# main.net
KiCad netlist of a schematic drawn in Altium Designer
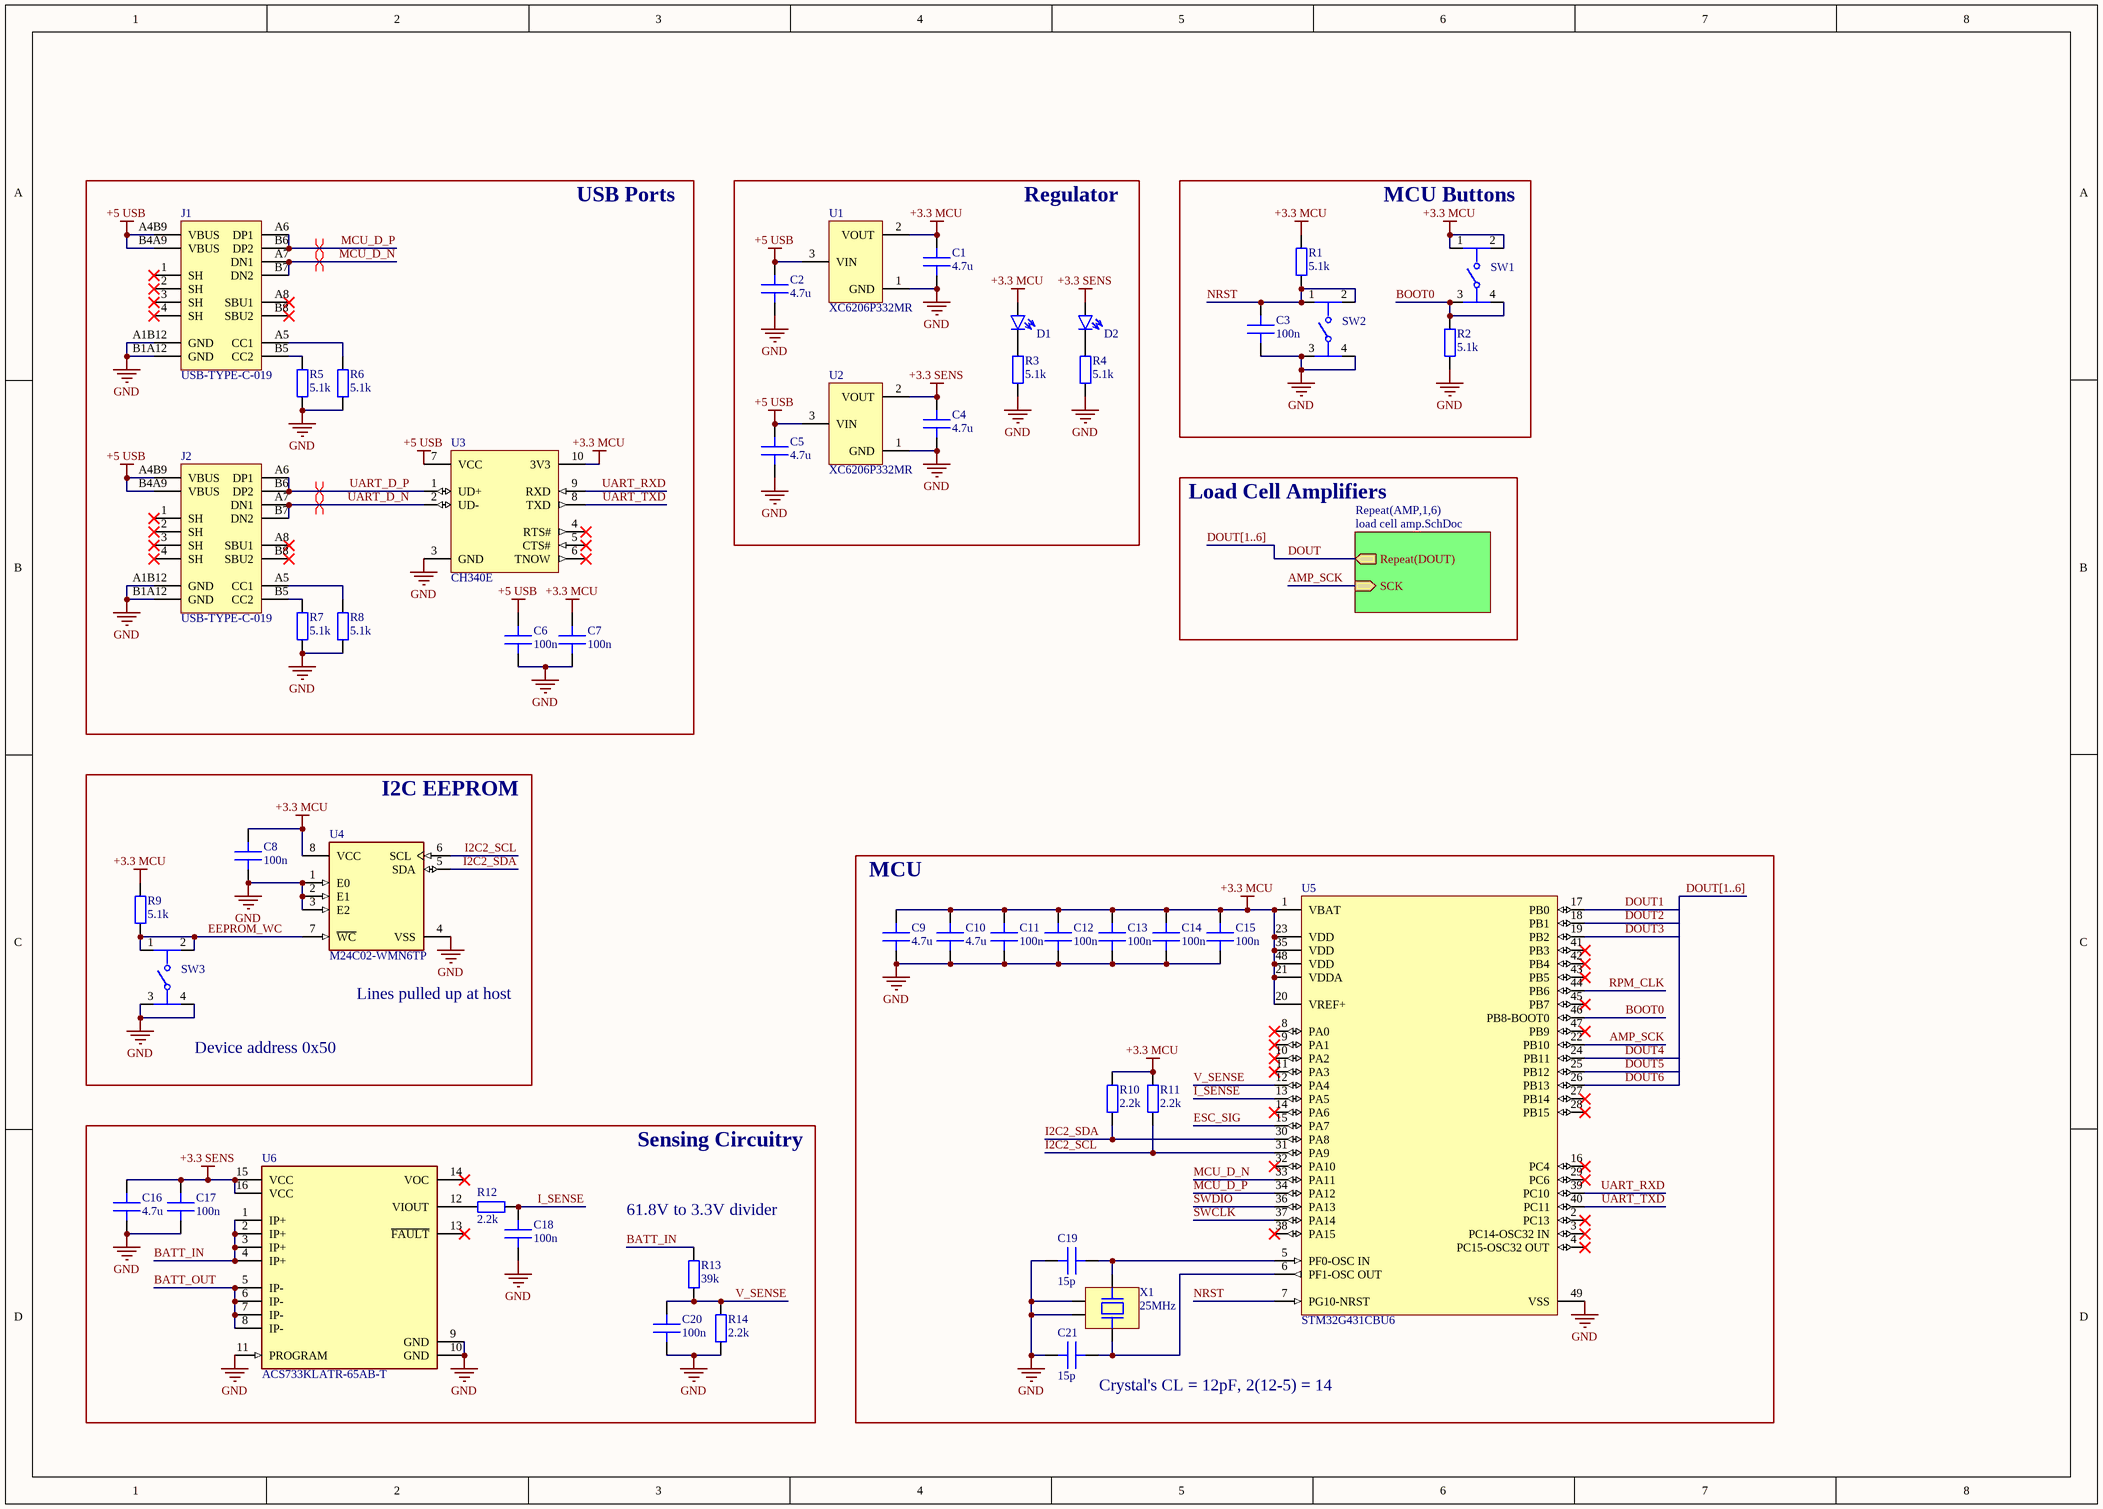
[diagram p0: main.SchDoc]

(export (version "E")
  (design (tool "Eeschema 10.0.6"))
  (components
    (comp (ref "C1")
      (value "4.7u")
      (footprint "IPC C C0603 NO SILK")
      (libsource (lib "JLCPCB Library") (part "Generic CAP 0603"))
    )
    (comp (ref "C2")
      (value "4.7u")
      (footprint "IPC C C0603 NO SILK")
      (libsource (lib "JLCPCB Library") (part "Generic CAP 0603"))
    )
    (comp (ref "C3")
      (value "100n")
      (footprint "IPC C C0402 NO SILK")
      (libsource (lib "JLCPCB Library") (part "Generic CAP 0402"))
    )
    (comp (ref "C4")
      (value "4.7u")
      (footprint "IPC C C0603 NO SILK")
      (libsource (lib "JLCPCB Library") (part "Generic CAP 0603"))
    )
    (comp (ref "C5")
      (value "4.7u")
      (footprint "IPC C C0603 NO SILK")
      (libsource (lib "JLCPCB Library") (part "Generic CAP 0603"))
    )
    (comp (ref "C6")
      (value "100n")
      (footprint "IPC C C0402 NO SILK")
      (libsource (lib "JLCPCB Library") (part "Generic CAP 0402"))
    )
    (comp (ref "C7")
      (value "100n")
      (footprint "IPC C C0402 NO SILK")
      (libsource (lib "JLCPCB Library") (part "Generic CAP 0402"))
    )
    (comp (ref "C8")
      (value "100n")
      (footprint "IPC C C0402 NO SILK")
      (libsource (lib "JLCPCB Library") (part "Generic CAP 0402"))
    )
    (comp (ref "C9")
      (value "4.7u")
      (footprint "IPC C C0603 NO SILK")
      (libsource (lib "JLCPCB Library") (part "Generic CAP 0603"))
    )
    (comp (ref "C10")
      (value "4.7u")
      (footprint "IPC C C0603 NO SILK")
      (libsource (lib "JLCPCB Library") (part "Generic CAP 0603"))
    )
    (comp (ref "C11")
      (value "100n")
      (footprint "IPC C C0402 NO SILK")
      (libsource (lib "JLCPCB Library") (part "Generic CAP 0402"))
    )
    (comp (ref "C12")
      (value "100n")
      (footprint "IPC C C0402 NO SILK")
      (libsource (lib "JLCPCB Library") (part "Generic CAP 0402"))
    )
    (comp (ref "C13")
      (value "100n")
      (footprint "IPC C C0402 NO SILK")
      (libsource (lib "JLCPCB Library") (part "Generic CAP 0402"))
    )
    (comp (ref "C14")
      (value "100n")
      (footprint "IPC C C0402 NO SILK")
      (libsource (lib "JLCPCB Library") (part "Generic CAP 0402"))
    )
    (comp (ref "C15")
      (value "100n")
      (footprint "IPC C C0402 NO SILK")
      (libsource (lib "JLCPCB Library") (part "Generic CAP 0402"))
    )
    (comp (ref "C16")
      (value "4.7u")
      (footprint "IPC C C0603 NO SILK")
      (libsource (lib "JLCPCB Library") (part "Generic CAP 0603"))
    )
    (comp (ref "C17")
      (value "100n")
      (footprint "IPC C C0402 NO SILK")
      (libsource (lib "JLCPCB Library") (part "Generic CAP 0402"))
    )
    (comp (ref "C18")
      (value "100n")
      (footprint "IPC C C0402 NO SILK")
      (libsource (lib "JLCPCB Library") (part "Generic CAP 0402"))
    )
    (comp (ref "C19")
      (value "15p")
      (footprint "IPC C C0402 NO SILK")
      (libsource (lib "JLCPCB Library") (part "Generic CAP 0402"))
    )
    (comp (ref "C20")
      (value "100n")
      (footprint "IPC C C0402 NO SILK")
      (libsource (lib "JLCPCB Library") (part "Generic CAP 0402"))
    )
    (comp (ref "C21")
      (value "15p")
      (footprint "IPC C C0402 NO SILK")
      (libsource (lib "JLCPCB Library") (part "Generic CAP 0402"))
    )
    (comp (ref "D1")
      (value "Generic LED 0603")
      (footprint "IPC C D0603")
      (libsource (lib "JLCPCB Library") (part "Generic LED 0603"))
    )
    (comp (ref "D2")
      (value "Generic LED 0603")
      (footprint "IPC C D0603")
      (libsource (lib "JLCPCB Library") (part "Generic LED 0603"))
    )
    (comp (ref "J1")
      (value "USB-TYPE-C-019")
      (footprint "USB-TYPE-C-12+4P")
      (fields (field (name "MANUFACTURER") "DEALON(德艺隆)"))
      (libsource (lib "JLCPCB Library") (part "USB-TYPE-C-019"))
    )
    (comp (ref "J2")
      (value "USB-TYPE-C-019")
      (footprint "USB-TYPE-C-12+4P")
      (fields (field (name "MANUFACTURER") "DEALON(德艺隆)"))
      (libsource (lib "JLCPCB Library") (part "USB-TYPE-C-019"))
    )
    (comp (ref "R1")
      (value "5.1k")
      (footprint "IPC C R0402 NO SILK")
      (libsource (lib "JLCPCB Library") (part "Generic RES 0402"))
    )
    (comp (ref "R2")
      (value "5.1k")
      (footprint "IPC C R0402 NO SILK")
      (libsource (lib "JLCPCB Library") (part "Generic RES 0402"))
    )
    (comp (ref "R3")
      (value "5.1k")
      (footprint "IPC C R0402 NO SILK")
      (libsource (lib "JLCPCB Library") (part "Generic RES 0402"))
    )
    (comp (ref "R4")
      (value "5.1k")
      (footprint "IPC C R0402 NO SILK")
      (libsource (lib "JLCPCB Library") (part "Generic RES 0402"))
    )
    (comp (ref "R5")
      (value "5.1k")
      (footprint "IPC C R0402 NO SILK")
      (libsource (lib "JLCPCB Library") (part "Generic RES 0402"))
    )
    (comp (ref "R6")
      (value "5.1k")
      (footprint "IPC C R0402 NO SILK")
      (libsource (lib "JLCPCB Library") (part "Generic RES 0402"))
    )
    (comp (ref "R7")
      (value "5.1k")
      (footprint "IPC C R0402 NO SILK")
      (libsource (lib "JLCPCB Library") (part "Generic RES 0402"))
    )
    (comp (ref "R8")
      (value "5.1k")
      (footprint "IPC C R0402 NO SILK")
      (libsource (lib "JLCPCB Library") (part "Generic RES 0402"))
    )
    (comp (ref "R9")
      (value "5.1k")
      (footprint "IPC C R0402 NO SILK")
      (libsource (lib "JLCPCB Library") (part "Generic RES 0402"))
    )
    (comp (ref "R10")
      (value "2.2k")
      (footprint "IPC C R0402 NO SILK")
      (libsource (lib "JLCPCB Library") (part "Generic RES 0402"))
    )
    (comp (ref "R11")
      (value "2.2k")
      (footprint "IPC C R0402 NO SILK")
      (libsource (lib "JLCPCB Library") (part "Generic RES 0402"))
    )
    (comp (ref "R12")
      (value "2.2k")
      (footprint "IPC C R0402 NO SILK")
      (libsource (lib "JLCPCB Library") (part "Generic RES 0402"))
    )
    (comp (ref "R13")
      (value "39k")
      (footprint "IPC C R0402 NO SILK")
      (libsource (lib "JLCPCB Library") (part "Generic RES 0402"))
    )
    (comp (ref "R14")
      (value "2.2k")
      (footprint "IPC C R0402 NO SILK")
      (libsource (lib "JLCPCB Library") (part "Generic RES 0402"))
    )
    (comp (ref "SW1")
      (value "PTS810SJM250SMTRLFS")
      (footprint "FP-PTS810SJM250SMTRLFS-MFG")
      (description "SWITCH TACTILE SPST-NO 0.05A 16V")
      (libsource (lib "Altium Content Vault") (part "1adf0dd01260c80cf25a44bfd6b99ba"))
    )
    (comp (ref "SW2")
      (value "PTS810SJM250SMTRLFS")
      (footprint "FP-PTS810SJM250SMTRLFS-MFG")
      (description "SWITCH TACTILE SPST-NO 0.05A 16V")
      (libsource (lib "Altium Content Vault") (part "1adf0dd01260c80cf25a44bfd6b99ba"))
    )
    (comp (ref "SW3")
      (value "PTS810SJM250SMTRLFS")
      (footprint "FP-PTS810SJM250SMTRLFS-MFG")
      (description "SWITCH TACTILE SPST-NO 0.05A 16V")
      (libsource (lib "Altium Content Vault") (part "1adf0dd01260c80cf25a44bfd6b99ba"))
    )
    (comp (ref "U1")
      (value "XC6206P332MR")
      (footprint "SOT23-3")
      (fields (field (name "MANUFACTURER") "TOREX(特瑞仕)"))
      (libsource (lib "JLCPCB Library") (part "3.3V Regulator XC6206P332MR_C5446"))
    )
    (comp (ref "U2")
      (value "XC6206P332MR")
      (footprint "SOT23-3")
      (fields (field (name "MANUFACTURER") "TOREX(特瑞仕)"))
      (libsource (lib "JLCPCB Library") (part "3.3V Regulator XC6206P332MR_C5446"))
    )
    (comp (ref "U3")
      (value "CH340E")
      (footprint "MSOP-UN10_L")
      (libsource (lib "JLCPCB Library") (part "CH340E"))
    )
    (comp (ref "U4")
      (value "M24C02-WMN6TP")
      (footprint "FP-SO8N-SO-A-MFG")
      (description "IC EEPROM 2K I2C 400KHZ 8SO")
      (fields
        (field (name "MANUFACTURER") "STMicroelectronics")
        (field (name "OCTOPART") "https://octopart.com/m24c02-wmn6tp-stmicroelectronics-55404516")
      )
      (libsource (lib "Altium Content Vault") (part "6c91e1c1613830ec3abd94c18390ae3"))
    )
    (comp (ref "U5")
      (value "STM32G431CBU6")
      (footprint "QFN50P700X700X60_HS-49L")
      (libsource (lib "JLCPCB Library") (part "STM32G431CBU6"))
    )
    (comp (ref "U6")
      (value "ACS733KLATR-65AB-T")
      (footprint "FP-LA-16-MFG")
      (description "AUTOMOTIVE GRADE HIGH BANDWIDTH")
      (libsource (lib "Altium Content Vault") (part "bea2a1565df5e50c2a3c76684115569"))
    )
    (comp (ref "X1")
      (value "25MHz")
      (footprint "OSC-SMD_4P-L3.2-W2.5-BL")
      (fields (field (name "MANUFACTURER") "YXC(扬兴晶振)") (field (name "MANUFACTURER PART") "X322525MOB4SI"))
      (libsource (lib "JLCPCB Library") (part "Crystal 25MHz X322525MOB4SI"))
    )
  )
  (nets
    (net (code "1") (name "+3.3 MCU") (class "Default")
      (node (ref "C1") (pin "2") (pinfunction "2_2") (pintype "passive"))
      (node (ref "C10") (pin "2") (pinfunction "2_2") (pintype "passive"))
      (node (ref "C11") (pin "2") (pinfunction "2_2") (pintype "passive"))
      (node (ref "C12") (pin "2") (pinfunction "2_2") (pintype "passive"))
      (node (ref "C13") (pin "2") (pinfunction "2_2") (pintype "passive"))
      (node (ref "C14") (pin "2") (pinfunction "2_2") (pintype "passive"))
      (node (ref "C15") (pin "2") (pinfunction "2_2") (pintype "passive"))
      (node (ref "C7") (pin "2") (pinfunction "2_2") (pintype "passive"))
      (node (ref "C8") (pin "2") (pinfunction "2_2") (pintype "passive"))
      (node (ref "C9") (pin "2") (pinfunction "2_2") (pintype "passive"))
      (node (ref "D1") (pin "1") (pinfunction "A_1") (pintype "passive"))
      (node (ref "R1") (pin "2") (pinfunction "2_2") (pintype "passive"))
      (node (ref "R10") (pin "2") (pinfunction "2_2") (pintype "passive"))
      (node (ref "R11") (pin "2") (pinfunction "2_2") (pintype "passive"))
      (node (ref "R9") (pin "2") (pinfunction "2_2") (pintype "passive"))
      (node (ref "SW1") (pin "1") (pinfunction "1_1") (pintype "passive"))
      (node (ref "SW1") (pin "2") (pinfunction "2_2") (pintype "passive"))
      (node (ref "U1") (pin "2") (pinfunction "VOUT_2") (pintype "power_in"))
      (node (ref "U3") (pin "10") (pinfunction "3V3_10") (pintype "power_in"))
      (node (ref "U4") (pin "8") (pinfunction "VCC_8") (pintype "power_in"))
      (node (ref "U5") (pin "1") (pinfunction "VBAT_1") (pintype "power_in"))
      (node (ref "U5") (pin "20") (pinfunction "VREF+_20") (pintype "passive"))
      (node (ref "U5") (pin "21") (pinfunction "VDDA_21") (pintype "power_in"))
      (node (ref "U5") (pin "23") (pinfunction "VDD_23") (pintype "power_in"))
      (node (ref "U5") (pin "35") (pinfunction "VDD_35") (pintype "power_in"))
      (node (ref "U5") (pin "48") (pinfunction "VDD_48") (pintype "power_in"))
    )
    (net (code "2") (name "+3.3 SENS") (class "Default")
      (node (ref "C16") (pin "2") (pinfunction "2_2") (pintype "passive"))
      (node (ref "C17") (pin "2") (pinfunction "2_2") (pintype "passive"))
      (node (ref "C4") (pin "2") (pinfunction "2_2") (pintype "passive"))
      (node (ref "D2") (pin "1") (pinfunction "A_1") (pintype "passive"))
      (node (ref "U2") (pin "2") (pinfunction "VOUT_2") (pintype "power_in"))
      (node (ref "U6") (pin "15") (pinfunction "VCC_15") (pintype "power_in"))
      (node (ref "U6") (pin "16") (pinfunction "VCC_16") (pintype "power_in"))
    )
    (net (code "3") (name "+5 USB") (class "Default")
      (node (ref "C2") (pin "2") (pinfunction "2_2") (pintype "passive"))
      (node (ref "C5") (pin "2") (pinfunction "2_2") (pintype "passive"))
      (node (ref "C6") (pin "2") (pinfunction "2_2") (pintype "passive"))
      (node (ref "J1") (pin "A4B9") (pinfunction "VBUS_A4B9") (pintype "power_in"))
      (node (ref "J1") (pin "B4A9") (pinfunction "VBUS_B4A9") (pintype "power_in"))
      (node (ref "J2") (pin "A4B9") (pinfunction "VBUS_A4B9") (pintype "power_in"))
      (node (ref "J2") (pin "B4A9") (pinfunction "VBUS_B4A9") (pintype "power_in"))
      (node (ref "U1") (pin "3") (pinfunction "VIN_3") (pintype "power_in"))
      (node (ref "U2") (pin "3") (pinfunction "VIN_3") (pintype "power_in"))
      (node (ref "U3") (pin "7") (pinfunction "VCC_7") (pintype "power_in"))
    )
    (net (code "4") (name "/AMP_SCK") (class "Default")
      (node (ref "U5") (pin "22") (pinfunction "PB10_22") (pintype "bidirectional"))
    )
    (net (code "5") (name "/BATT_IN") (class "Default")
      (node (ref "R13") (pin "2") (pinfunction "2_2") (pintype "passive"))
      (node (ref "U6") (pin "1") (pinfunction "IP+_1") (pintype "passive"))
      (node (ref "U6") (pin "2") (pinfunction "IP+_2") (pintype "passive"))
      (node (ref "U6") (pin "3") (pinfunction "IP+_3") (pintype "passive"))
      (node (ref "U6") (pin "4") (pinfunction "IP+_4") (pintype "passive"))
    )
    (net (code "6") (name "/BATT_OUT") (class "Default")
      (node (ref "U6") (pin "5") (pinfunction "IP-_5") (pintype "passive"))
      (node (ref "U6") (pin "6") (pinfunction "IP-_6") (pintype "passive"))
      (node (ref "U6") (pin "7") (pinfunction "IP-_7") (pintype "passive"))
      (node (ref "U6") (pin "8") (pinfunction "IP-_8") (pintype "passive"))
    )
    (net (code "7") (name "/BOOT0") (class "Default")
      (node (ref "R2") (pin "2") (pinfunction "2_2") (pintype "passive"))
      (node (ref "SW1") (pin "3") (pinfunction "3_3") (pintype "passive"))
      (node (ref "SW1") (pin "4") (pinfunction "4_4") (pintype "passive"))
      (node (ref "U5") (pin "46") (pinfunction "PB8-BOOT0_46") (pintype "bidirectional"))
    )
    (net (code "9") (name "/DOUT1") (class "Default")
      (node (ref "U5") (pin "17") (pinfunction "PB0_17") (pintype "bidirectional"))
    )
    (net (code "10") (name "/DOUT2") (class "Default")
      (node (ref "U5") (pin "18") (pinfunction "PB1_18") (pintype "bidirectional"))
    )
    (net (code "11") (name "/DOUT3") (class "Default")
      (node (ref "U5") (pin "19") (pinfunction "PB2_19") (pintype "bidirectional"))
    )
    (net (code "12") (name "/DOUT4") (class "Default")
      (node (ref "U5") (pin "24") (pinfunction "PB11_24") (pintype "bidirectional"))
    )
    (net (code "13") (name "/DOUT5") (class "Default")
      (node (ref "U5") (pin "25") (pinfunction "PB12_25") (pintype "bidirectional"))
    )
    (net (code "14") (name "/DOUT6") (class "Default")
      (node (ref "U5") (pin "26") (pinfunction "PB13_26") (pintype "bidirectional"))
    )
    (net (code "16") (name "/EEPROM_WC") (class "Default")
      (node (ref "R9") (pin "1") (pinfunction "1_1") (pintype "passive"))
      (node (ref "SW3") (pin "1") (pinfunction "1_1") (pintype "passive"))
      (node (ref "SW3") (pin "2") (pinfunction "2_2") (pintype "passive"))
      (node (ref "U4") (pin "7") (pinfunction "~{WC}_7") (pintype "input"))
    )
    (net (code "17") (name "/ESC_SIG") (class "Default")
      (node (ref "U5") (pin "15") (pinfunction "PA7_15") (pintype "bidirectional"))
    )
    (net (code "18") (name "/I2C2_SCL") (class "Default")
      (node (ref "R11") (pin "1") (pinfunction "1_1") (pintype "passive"))
      (node (ref "U4") (pin "6") (pinfunction "SCL_6") (pintype "input"))
      (node (ref "U5") (pin "31") (pinfunction "PA9_31") (pintype "bidirectional"))
    )
    (net (code "19") (name "/I2C2_SDA") (class "Default")
      (node (ref "R10") (pin "1") (pinfunction "1_1") (pintype "passive"))
      (node (ref "U4") (pin "5") (pinfunction "SDA_5") (pintype "bidirectional"))
      (node (ref "U5") (pin "30") (pinfunction "PA8_30") (pintype "bidirectional"))
    )
    (net (code "20") (name "/I_SENSE") (class "Default")
      (node (ref "C18") (pin "2") (pinfunction "2_2") (pintype "passive"))
      (node (ref "R12") (pin "1") (pinfunction "1_1") (pintype "passive"))
      (node (ref "U5") (pin "13") (pinfunction "PA5_13") (pintype "bidirectional"))
    )
    (net (code "21") (name "/MCU_D_N") (class "Default")
      (node (ref "J1") (pin "A7") (pinfunction "DN1_A7") (pintype "passive"))
      (node (ref "J1") (pin "B7") (pinfunction "DN2_B7") (pintype "passive"))
      (node (ref "U5") (pin "33") (pinfunction "PA11_33") (pintype "bidirectional"))
    )
    (net (code "22") (name "/MCU_D_P") (class "Default")
      (node (ref "J1") (pin "A6") (pinfunction "DP1_A6") (pintype "passive"))
      (node (ref "J1") (pin "B6") (pinfunction "DP2_B6") (pintype "passive"))
      (node (ref "U5") (pin "34") (pinfunction "PA12_34") (pintype "bidirectional"))
    )
    (net (code "23") (name "/NRST") (class "Default")
      (node (ref "C3") (pin "2") (pinfunction "2_2") (pintype "passive"))
      (node (ref "R1") (pin "1") (pinfunction "1_1") (pintype "passive"))
      (node (ref "SW2") (pin "1") (pinfunction "1_1") (pintype "passive"))
      (node (ref "SW2") (pin "2") (pinfunction "2_2") (pintype "passive"))
      (node (ref "U5") (pin "7") (pinfunction "PG10-NRST_7") (pintype "input"))
    )
    (net (code "24") (name "/RPM_CLK") (class "Default")
      (node (ref "U5") (pin "44") (pinfunction "PB6_44") (pintype "bidirectional"))
    )
    (net (code "25") (name "/SWCLK") (class "Default")
      (node (ref "U5") (pin "37") (pinfunction "PA14_37") (pintype "bidirectional"))
    )
    (net (code "26") (name "/SWDIO") (class "Default")
      (node (ref "U5") (pin "36") (pinfunction "PA13_36") (pintype "bidirectional"))
    )
    (net (code "27") (name "/UART_D_N") (class "Default")
      (node (ref "J2") (pin "A7") (pinfunction "DN1_A7") (pintype "passive"))
      (node (ref "J2") (pin "B7") (pinfunction "DN2_B7") (pintype "passive"))
      (node (ref "U3") (pin "2") (pinfunction "UD-_2") (pintype "bidirectional"))
    )
    (net (code "28") (name "/UART_D_P") (class "Default")
      (node (ref "J2") (pin "A6") (pinfunction "DP1_A6") (pintype "passive"))
      (node (ref "J2") (pin "B6") (pinfunction "DP2_B6") (pintype "passive"))
      (node (ref "U3") (pin "1") (pinfunction "UD+_1") (pintype "bidirectional"))
    )
    (net (code "29") (name "/UART_RXD") (class "Default")
      (node (ref "U3") (pin "9") (pinfunction "RXD_9") (pintype "input"))
      (node (ref "U5") (pin "39") (pinfunction "PC10_39") (pintype "bidirectional"))
    )
    (net (code "30") (name "/UART_TXD") (class "Default")
      (node (ref "U3") (pin "8") (pinfunction "TXD_8") (pintype "output"))
      (node (ref "U5") (pin "40") (pinfunction "PC11_40") (pintype "bidirectional"))
    )
    (net (code "31") (name "/V_SENSE") (class "Default")
      (node (ref "C20") (pin "2") (pinfunction "2_2") (pintype "passive"))
      (node (ref "R13") (pin "1") (pinfunction "1_1") (pintype "passive"))
      (node (ref "R14") (pin "2") (pinfunction "2_2") (pintype "passive"))
      (node (ref "U5") (pin "12") (pinfunction "PA4_12") (pintype "bidirectional"))
    )
    (net (code "32") (name "GND") (class "Default")
      (node (ref "C1") (pin "1") (pinfunction "1_1") (pintype "passive"))
      (node (ref "C10") (pin "1") (pinfunction "1_1") (pintype "passive"))
      (node (ref "C11") (pin "1") (pinfunction "1_1") (pintype "passive"))
      (node (ref "C12") (pin "1") (pinfunction "1_1") (pintype "passive"))
      (node (ref "C13") (pin "1") (pinfunction "1_1") (pintype "passive"))
      (node (ref "C14") (pin "1") (pinfunction "1_1") (pintype "passive"))
      (node (ref "C15") (pin "1") (pinfunction "1_1") (pintype "passive"))
      (node (ref "C16") (pin "1") (pinfunction "1_1") (pintype "passive"))
      (node (ref "C17") (pin "1") (pinfunction "1_1") (pintype "passive"))
      (node (ref "C18") (pin "1") (pinfunction "1_1") (pintype "passive"))
      (node (ref "C19") (pin "2") (pinfunction "2_2") (pintype "passive"))
      (node (ref "C2") (pin "1") (pinfunction "1_1") (pintype "passive"))
      (node (ref "C20") (pin "1") (pinfunction "1_1") (pintype "passive"))
      (node (ref "C21") (pin "2") (pinfunction "2_2") (pintype "passive"))
      (node (ref "C3") (pin "1") (pinfunction "1_1") (pintype "passive"))
      (node (ref "C4") (pin "1") (pinfunction "1_1") (pintype "passive"))
      (node (ref "C5") (pin "1") (pinfunction "1_1") (pintype "passive"))
      (node (ref "C6") (pin "1") (pinfunction "1_1") (pintype "passive"))
      (node (ref "C7") (pin "1") (pinfunction "1_1") (pintype "passive"))
      (node (ref "C8") (pin "1") (pinfunction "1_1") (pintype "passive"))
      (node (ref "C9") (pin "1") (pinfunction "1_1") (pintype "passive"))
      (node (ref "J1") (pin "A1B12") (pinfunction "GND_A1B12") (pintype "power_in"))
      (node (ref "J1") (pin "B1A12") (pinfunction "GND_B1A12") (pintype "power_in"))
      (node (ref "J2") (pin "A1B12") (pinfunction "GND_A1B12") (pintype "power_in"))
      (node (ref "J2") (pin "B1A12") (pinfunction "GND_B1A12") (pintype "power_in"))
      (node (ref "R14") (pin "1") (pinfunction "1_1") (pintype "passive"))
      (node (ref "R2") (pin "1") (pinfunction "1_1") (pintype "passive"))
      (node (ref "R3") (pin "1") (pinfunction "1_1") (pintype "passive"))
      (node (ref "R4") (pin "1") (pinfunction "1_1") (pintype "passive"))
      (node (ref "R5") (pin "1") (pinfunction "1_1") (pintype "passive"))
      (node (ref "R6") (pin "1") (pinfunction "1_1") (pintype "passive"))
      (node (ref "R7") (pin "1") (pinfunction "1_1") (pintype "passive"))
      (node (ref "R8") (pin "1") (pinfunction "1_1") (pintype "passive"))
      (node (ref "SW2") (pin "3") (pinfunction "3_3") (pintype "passive"))
      (node (ref "SW2") (pin "4") (pinfunction "4_4") (pintype "passive"))
      (node (ref "SW3") (pin "3") (pinfunction "3_3") (pintype "passive"))
      (node (ref "SW3") (pin "4") (pinfunction "4_4") (pintype "passive"))
      (node (ref "U1") (pin "1") (pinfunction "GND_1") (pintype "power_in"))
      (node (ref "U2") (pin "1") (pinfunction "GND_1") (pintype "power_in"))
      (node (ref "U3") (pin "3") (pinfunction "GND_3") (pintype "power_in"))
      (node (ref "U4") (pin "1") (pinfunction "E0_1") (pintype "input"))
      (node (ref "U4") (pin "2") (pinfunction "E1_2") (pintype "input"))
      (node (ref "U4") (pin "3") (pinfunction "E2_3") (pintype "input"))
      (node (ref "U4") (pin "4") (pinfunction "VSS_4") (pintype "power_in"))
      (node (ref "U5") (pin "49") (pinfunction "VSS_49") (pintype "power_in"))
      (node (ref "U6") (pin "10") (pinfunction "GND_10") (pintype "power_in"))
      (node (ref "U6") (pin "11") (pinfunction "PROGRAM_11") (pintype "input"))
      (node (ref "U6") (pin "9") (pinfunction "GND_9") (pintype "power_in"))
      (node (ref "X1") (pin "2") (pinfunction "2_2") (pintype "passive"))
      (node (ref "X1") (pin "4") (pinfunction "4_4") (pintype "passive"))
    )
    (net (code "33") (name "Net-(D1-C)") (class "Default")
      (node (ref "D1") (pin "2") (pinfunction "C_2") (pintype "passive"))
      (node (ref "R3") (pin "2") (pinfunction "2_2") (pintype "passive"))
    )
    (net (code "34") (name "Net-(D2-C)") (class "Default")
      (node (ref "D2") (pin "2") (pinfunction "C_2") (pintype "passive"))
      (node (ref "R4") (pin "2") (pinfunction "2_2") (pintype "passive"))
    )
    (net (code "35") (name "Net-(J1-CC1)") (class "Default")
      (node (ref "J1") (pin "A5") (pinfunction "CC1_A5") (pintype "passive"))
      (node (ref "R6") (pin "2") (pinfunction "2_2") (pintype "passive"))
    )
    (net (code "36") (name "Net-(J1-CC2)") (class "Default")
      (node (ref "J1") (pin "B5") (pinfunction "CC2_B5") (pintype "passive"))
      (node (ref "R5") (pin "2") (pinfunction "2_2") (pintype "passive"))
    )
    (net (code "37") (name "Net-(J2-CC1)") (class "Default")
      (node (ref "J2") (pin "A5") (pinfunction "CC1_A5") (pintype "passive"))
      (node (ref "R8") (pin "2") (pinfunction "2_2") (pintype "passive"))
    )
    (net (code "38") (name "Net-(J2-CC2)") (class "Default")
      (node (ref "J2") (pin "B5") (pinfunction "CC2_B5") (pintype "passive"))
      (node (ref "R7") (pin "2") (pinfunction "2_2") (pintype "passive"))
    )
    (net (code "39") (name "Net-(U5-PF0-OSC_IN)") (class "Default")
      (node (ref "C19") (pin "1") (pinfunction "1_1") (pintype "passive"))
      (node (ref "U5") (pin "5") (pinfunction "PF0-OSC_IN_5") (pintype "input"))
      (node (ref "X1") (pin "1") (pinfunction "1_1") (pintype "passive"))
    )
    (net (code "40") (name "Net-(U5-PF1-OSC_OUT)") (class "Default")
      (node (ref "C21") (pin "1") (pinfunction "1_1") (pintype "passive"))
      (node (ref "U5") (pin "6") (pinfunction "PF1-OSC_OUT_6") (pintype "output"))
      (node (ref "X1") (pin "3") (pinfunction "3_3") (pintype "passive"))
    )
    (net (code "41") (name "Net-(U6-VIOUT)") (class "Default")
      (node (ref "R12") (pin "2") (pinfunction "2_2") (pintype "passive"))
      (node (ref "U6") (pin "12") (pinfunction "VIOUT_12") (pintype "passive"))
    )
    (net (code "42") (name "unconnected-(J1-SBU1-PadA8)") (class "Default")
      (node (ref "J1") (pin "A8") (pinfunction "SBU1_A8") (pintype "passive+no_connect"))
    )
    (net (code "43") (name "unconnected-(J1-SBU2-PadB8)") (class "Default")
      (node (ref "J1") (pin "B8") (pinfunction "SBU2_B8") (pintype "passive+no_connect"))
    )
    (net (code "44") (name "unconnected-(J1-SH-Pad1)") (class "Default")
      (node (ref "J1") (pin "1") (pinfunction "SH_1") (pintype "passive+no_connect"))
    )
    (net (code "45") (name "unconnected-(J1-SH-Pad2)") (class "Default")
      (node (ref "J1") (pin "2") (pinfunction "SH_2") (pintype "passive+no_connect"))
    )
    (net (code "46") (name "unconnected-(J1-SH-Pad3)") (class "Default")
      (node (ref "J1") (pin "3") (pinfunction "SH_3") (pintype "passive+no_connect"))
    )
    (net (code "47") (name "unconnected-(J1-SH-Pad4)") (class "Default")
      (node (ref "J1") (pin "4") (pinfunction "SH_4") (pintype "passive+no_connect"))
    )
    (net (code "48") (name "unconnected-(J2-SBU1-PadA8)") (class "Default")
      (node (ref "J2") (pin "A8") (pinfunction "SBU1_A8") (pintype "passive+no_connect"))
    )
    (net (code "49") (name "unconnected-(J2-SBU2-PadB8)") (class "Default")
      (node (ref "J2") (pin "B8") (pinfunction "SBU2_B8") (pintype "passive+no_connect"))
    )
    (net (code "50") (name "unconnected-(J2-SH-Pad1)") (class "Default")
      (node (ref "J2") (pin "1") (pinfunction "SH_1") (pintype "passive+no_connect"))
    )
    (net (code "51") (name "unconnected-(J2-SH-Pad2)") (class "Default")
      (node (ref "J2") (pin "2") (pinfunction "SH_2") (pintype "passive+no_connect"))
    )
    (net (code "52") (name "unconnected-(J2-SH-Pad3)") (class "Default")
      (node (ref "J2") (pin "3") (pinfunction "SH_3") (pintype "passive+no_connect"))
    )
    (net (code "53") (name "unconnected-(J2-SH-Pad4)") (class "Default")
      (node (ref "J2") (pin "4") (pinfunction "SH_4") (pintype "passive+no_connect"))
    )
    (net (code "54") (name "unconnected-(U3-CTS#-Pad5)") (class "Default")
      (node (ref "U3") (pin "5") (pinfunction "CTS#_5") (pintype "input+no_connect"))
    )
    (net (code "55") (name "unconnected-(U3-RTS#-Pad4)") (class "Default")
      (node (ref "U3") (pin "4") (pinfunction "RTS#_4") (pintype "output+no_connect"))
    )
    (net (code "56") (name "unconnected-(U3-TNOW-Pad6)") (class "Default")
      (node (ref "U3") (pin "6") (pinfunction "TNOW_6") (pintype "output+no_connect"))
    )
    (net (code "57") (name "unconnected-(U5-PA0-Pad8)") (class "Default")
      (node (ref "U5") (pin "8") (pinfunction "PA0_8") (pintype "bidirectional+no_connect"))
    )
    (net (code "58") (name "unconnected-(U5-PA1-Pad9)") (class "Default")
      (node (ref "U5") (pin "9") (pinfunction "PA1_9") (pintype "bidirectional+no_connect"))
    )
    (net (code "59") (name "unconnected-(U5-PA2-Pad10)") (class "Default")
      (node (ref "U5") (pin "10") (pinfunction "PA2_10") (pintype "bidirectional+no_connect"))
    )
    (net (code "60") (name "unconnected-(U5-PA3-Pad11)") (class "Default")
      (node (ref "U5") (pin "11") (pinfunction "PA3_11") (pintype "bidirectional+no_connect"))
    )
    (net (code "61") (name "unconnected-(U5-PA6-Pad14)") (class "Default")
      (node (ref "U5") (pin "14") (pinfunction "PA6_14") (pintype "bidirectional+no_connect"))
    )
    (net (code "62") (name "unconnected-(U5-PA10-Pad32)") (class "Default")
      (node (ref "U5") (pin "32") (pinfunction "PA10_32") (pintype "bidirectional+no_connect"))
    )
    (net (code "63") (name "unconnected-(U5-PA15-Pad38)") (class "Default")
      (node (ref "U5") (pin "38") (pinfunction "PA15_38") (pintype "bidirectional+no_connect"))
    )
    (net (code "64") (name "unconnected-(U5-PB3-Pad41)") (class "Default")
      (node (ref "U5") (pin "41") (pinfunction "PB3_41") (pintype "bidirectional+no_connect"))
    )
    (net (code "65") (name "unconnected-(U5-PB4-Pad42)") (class "Default")
      (node (ref "U5") (pin "42") (pinfunction "PB4_42") (pintype "bidirectional+no_connect"))
    )
    (net (code "66") (name "unconnected-(U5-PB5-Pad43)") (class "Default")
      (node (ref "U5") (pin "43") (pinfunction "PB5_43") (pintype "bidirectional+no_connect"))
    )
    (net (code "67") (name "unconnected-(U5-PB7-Pad45)") (class "Default")
      (node (ref "U5") (pin "45") (pinfunction "PB7_45") (pintype "bidirectional+no_connect"))
    )
    (net (code "68") (name "unconnected-(U5-PB9-Pad47)") (class "Default")
      (node (ref "U5") (pin "47") (pinfunction "PB9_47") (pintype "bidirectional+no_connect"))
    )
    (net (code "69") (name "unconnected-(U5-PB14-Pad27)") (class "Default")
      (node (ref "U5") (pin "27") (pinfunction "PB14_27") (pintype "bidirectional+no_connect"))
    )
    (net (code "70") (name "unconnected-(U5-PB15-Pad28)") (class "Default")
      (node (ref "U5") (pin "28") (pinfunction "PB15_28") (pintype "bidirectional+no_connect"))
    )
    (net (code "71") (name "unconnected-(U5-PC4-Pad16)") (class "Default")
      (node (ref "U5") (pin "16") (pinfunction "PC4_16") (pintype "bidirectional+no_connect"))
    )
    (net (code "72") (name "unconnected-(U5-PC6-Pad29)") (class "Default")
      (node (ref "U5") (pin "29") (pinfunction "PC6_29") (pintype "bidirectional+no_connect"))
    )
    (net (code "73") (name "unconnected-(U5-PC13-Pad2)") (class "Default")
      (node (ref "U5") (pin "2") (pinfunction "PC13_2") (pintype "bidirectional+no_connect"))
    )
    (net (code "74") (name "unconnected-(U5-PC14-OSC32_IN-Pad3)") (class "Default")
      (node (ref "U5") (pin "3") (pinfunction "PC14-OSC32_IN_3") (pintype "bidirectional+no_connect"))
    )
    (net (code "75") (name "unconnected-(U5-PC15-OSC32_OUT-Pad4)") (class "Default")
      (node (ref "U5") (pin "4") (pinfunction "PC15-OSC32_OUT_4") (pintype "bidirectional+no_connect"))
    )
    (net (code "76") (name "unconnected-(U6-VOC-Pad14)") (class "Default")
      (node (ref "U6") (pin "14") (pinfunction "VOC_14") (pintype "passive+no_connect"))
    )
    (net (code "77") (name "unconnected-(U6-~{FAULT}-Pad13)") (class "Default")
      (node (ref "U6") (pin "13") (pinfunction "~{FAULT}_13") (pintype "open_collector+no_connect"))
    )
  )
)
